# Remote.net
KiCad netlist of a schematic drawn in EAGLE
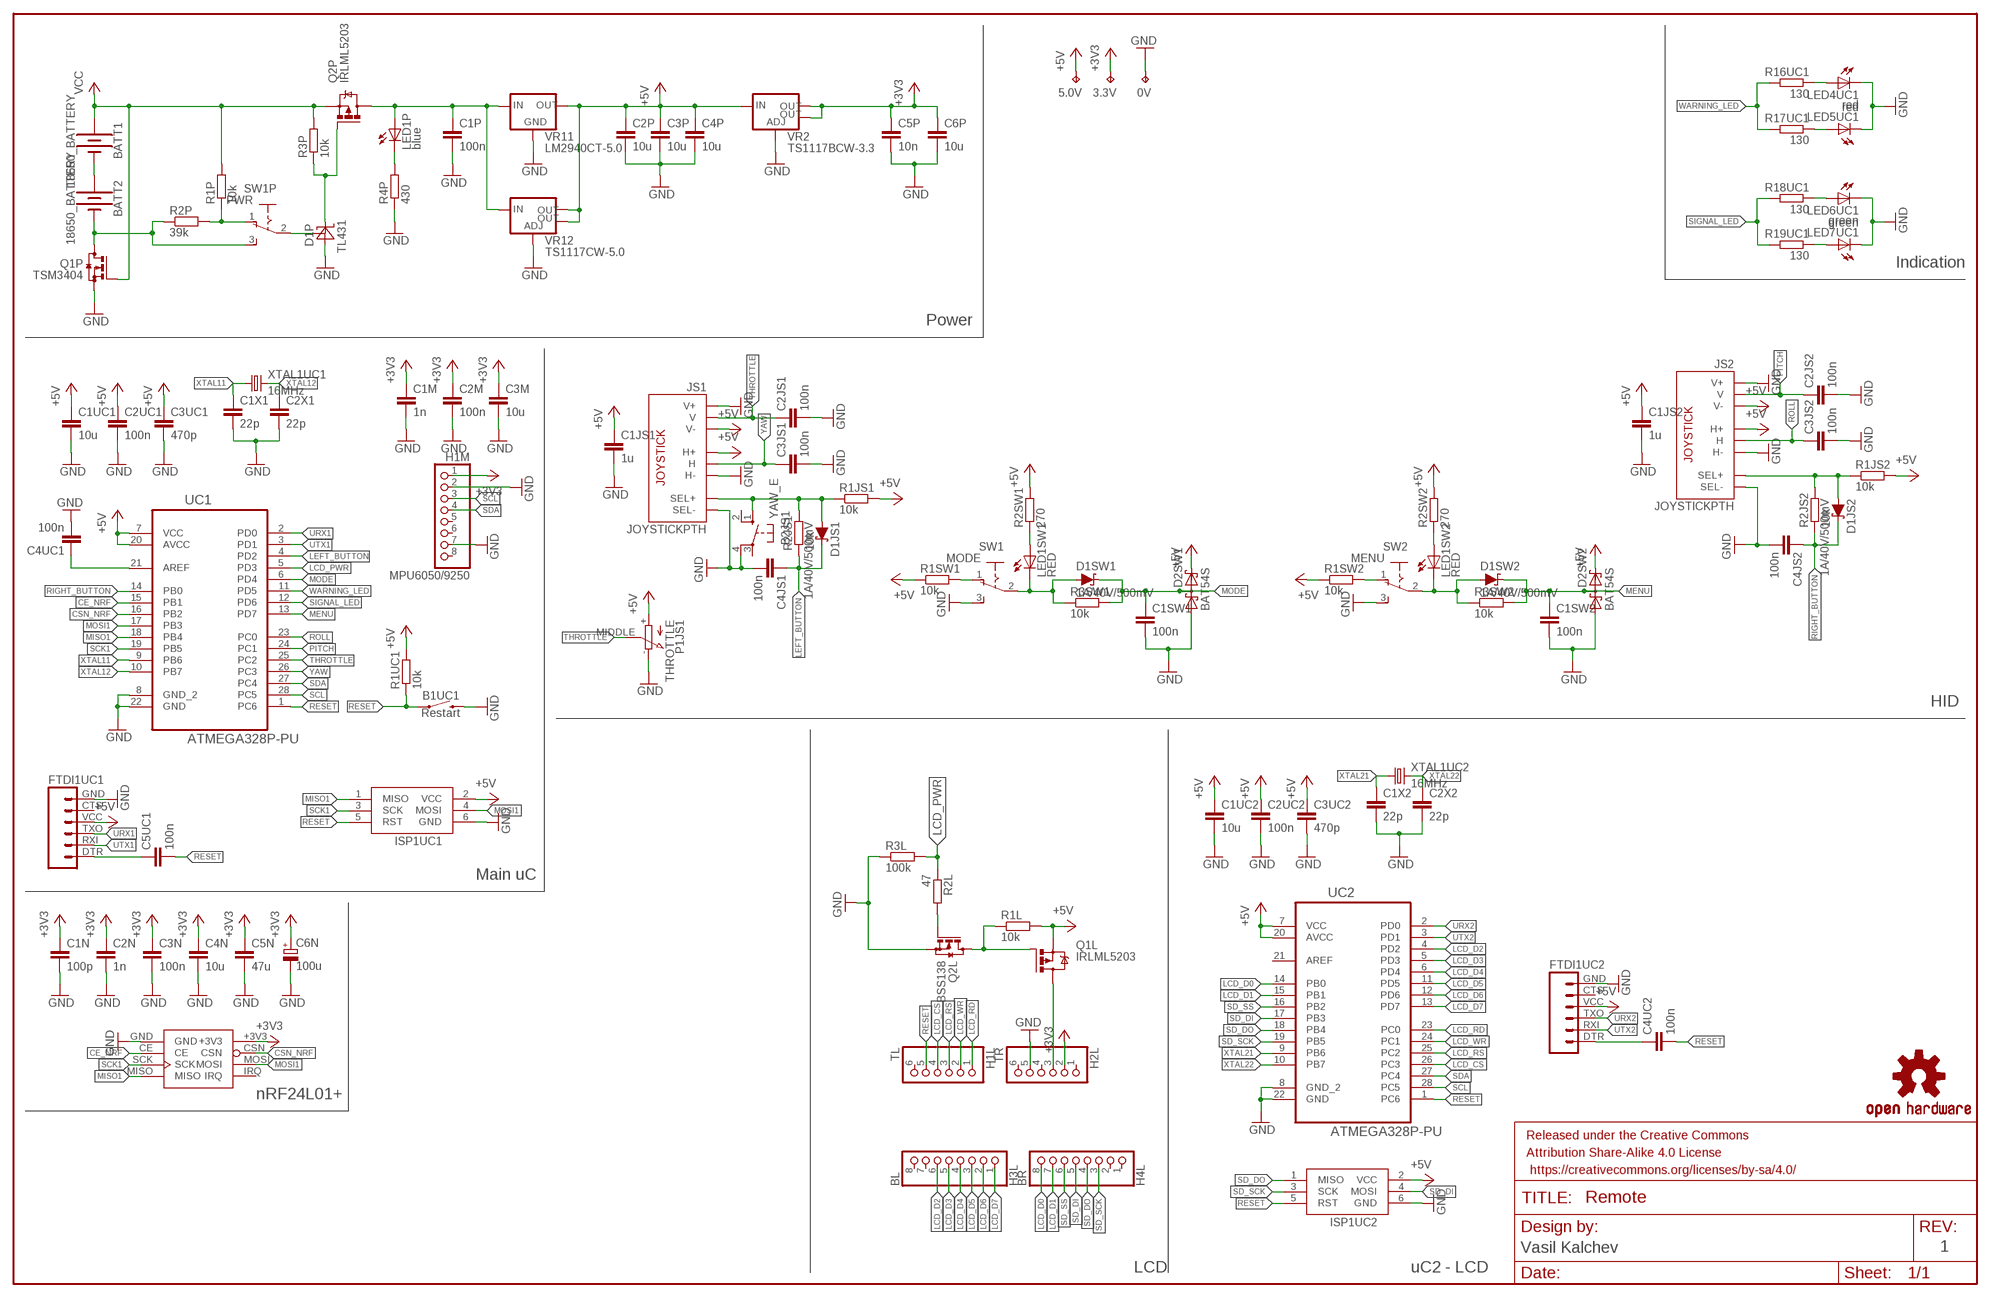
[diagram p0: schematic, sheet 1]

(export (version "E")
  (design (tool "Eeschema 10.0.6"))
  (components
    (comp (ref "0V")
      (value "TPTP10SQ")
      (footprint "eagle-import:TP10SQ")
      (libsource (lib "eagle-import") (part "TPTP10SQ"))
    )
    (comp (ref "3.3V")
      (value "TPTP10SQ")
      (footprint "eagle-import:TP10SQ")
      (libsource (lib "eagle-import") (part "TPTP10SQ"))
    )
    (comp (ref "5.0V")
      (value "TPTP10SQ")
      (footprint "eagle-import:TP10SQ")
      (libsource (lib "eagle-import") (part "TPTP10SQ"))
    )
    (comp (ref "B1")
      (value "nRF24L01+")
      (footprint "eagle-import:NRF24L01+_PA_LNA")
      (libsource (lib "eagle-import") (part "NRF24L01+_PA_LNA_BREAKOUT"))
    )
    (comp (ref "B1UC1")
      (value "Restart")
      (footprint "eagle-import:TACTILE_SWITCH_SMD_6.0X3.5MM")
      (libsource (lib "eagle-import") (part "MOMENTARY-SWITCH-SPST-SMD-6.0X3.5MM"))
    )
    (comp (ref "B2JS1")
      (value "YAW_E")
      (footprint "eagle-import:B3F-40XX")
      (fields (field (name "MF") "OMRON COMPONENTS USA") (field (name "MPN") "B3F-4000"))
      (libsource (lib "eagle-import") (part "40-XX"))
    )
    (comp (ref "BATT1")
      (value "18650_BATTERY")
      (footprint "eagle-import:BATTERY_HOLDER_18650")
      (libsource (lib "eagle-import") (part "18650_BATTERY"))
    )
    (comp (ref "BATT2")
      (value "18650_BATTERY")
      (footprint "eagle-import:BATTERY_HOLDER_18650")
      (libsource (lib "eagle-import") (part "18650_BATTERY"))
    )
    (comp (ref "C1JS1")
      (value "1u")
      (footprint "eagle-import:C1206")
      (libsource (lib "eagle-import") (part "C-EUC1206"))
    )
    (comp (ref "C1JS2")
      (value "1u")
      (footprint "eagle-import:C1206")
      (libsource (lib "eagle-import") (part "C-EUC1206"))
    )
    (comp (ref "C1M")
      (value "1n")
      (footprint "eagle-import:C1206")
      (libsource (lib "eagle-import") (part "C-EUC1206"))
    )
    (comp (ref "C1N")
      (value "100p")
      (footprint "eagle-import:C1206")
      (libsource (lib "eagle-import") (part "C-EUC1206"))
    )
    (comp (ref "C1P")
      (value "100n")
      (footprint "eagle-import:C1206")
      (libsource (lib "eagle-import") (part "C-EUC1206"))
    )
    (comp (ref "C1SW1")
      (value "100n")
      (footprint "eagle-import:C1206")
      (libsource (lib "eagle-import") (part "resistor_348_C-EUC1206"))
    )
    (comp (ref "C1SW2")
      (value "100n")
      (footprint "eagle-import:C1206")
      (libsource (lib "eagle-import") (part "resistor_348_C-EUC1206"))
    )
    (comp (ref "C1UC1")
      (value "10u")
      (footprint "eagle-import:C1206")
      (libsource (lib "eagle-import") (part "C-EUC1206"))
    )
    (comp (ref "C1UC2")
      (value "10u")
      (footprint "eagle-import:C1206")
      (libsource (lib "eagle-import") (part "C-EUC1206"))
    )
    (comp (ref "C1X1")
      (value "22p")
      (footprint "eagle-import:C1206")
      (libsource (lib "eagle-import") (part "C-EUC1206"))
    )
    (comp (ref "C1X2")
      (value "22p")
      (footprint "eagle-import:C1206")
      (libsource (lib "eagle-import") (part "C-EUC1206"))
    )
    (comp (ref "C2JS1")
      (value "100n")
      (footprint "eagle-import:C1206")
      (libsource (lib "eagle-import") (part "resistor_348_C-EUC1206"))
    )
    (comp (ref "C2JS2")
      (value "100n")
      (footprint "eagle-import:C1206")
      (libsource (lib "eagle-import") (part "resistor_348_C-EUC1206"))
    )
    (comp (ref "C2M")
      (value "100n")
      (footprint "eagle-import:C1206")
      (libsource (lib "eagle-import") (part "C-EUC1206"))
    )
    (comp (ref "C2N")
      (value "1n")
      (footprint "eagle-import:C1206")
      (libsource (lib "eagle-import") (part "C-EUC1206"))
    )
    (comp (ref "C2P")
      (value "10u")
      (footprint "eagle-import:C1206")
      (libsource (lib "eagle-import") (part "C-EUC1206"))
    )
    (comp (ref "C2UC1")
      (value "100n")
      (footprint "eagle-import:C1206")
      (libsource (lib "eagle-import") (part "C-EUC1206"))
    )
    (comp (ref "C2UC2")
      (value "100n")
      (footprint "eagle-import:C1206")
      (libsource (lib "eagle-import") (part "C-EUC1206"))
    )
    (comp (ref "C2X1")
      (value "22p")
      (footprint "eagle-import:C1206")
      (libsource (lib "eagle-import") (part "C-EUC1206"))
    )
    (comp (ref "C2X2")
      (value "22p")
      (footprint "eagle-import:C1206")
      (libsource (lib "eagle-import") (part "C-EUC1206"))
    )
    (comp (ref "C3JS1")
      (value "100n")
      (footprint "eagle-import:C1206")
      (libsource (lib "eagle-import") (part "resistor_348_C-EUC1206"))
    )
    (comp (ref "C3JS2")
      (value "100n")
      (footprint "eagle-import:C1206")
      (libsource (lib "eagle-import") (part "resistor_348_C-EUC1206"))
    )
    (comp (ref "C3M")
      (value "10u")
      (footprint "eagle-import:C1206")
      (libsource (lib "eagle-import") (part "C-EUC1206"))
    )
    (comp (ref "C3N")
      (value "100n")
      (footprint "eagle-import:C1206")
      (libsource (lib "eagle-import") (part "C-EUC1206"))
    )
    (comp (ref "C3P")
      (value "10u")
      (footprint "eagle-import:C1206")
      (libsource (lib "eagle-import") (part "C-EUC1206"))
    )
    (comp (ref "C3UC1")
      (value "470p")
      (footprint "eagle-import:C1206")
      (libsource (lib "eagle-import") (part "C-EUC1206"))
    )
    (comp (ref "C3UC2")
      (value "470p")
      (footprint "eagle-import:C1206")
      (libsource (lib "eagle-import") (part "C-EUC1206"))
    )
    (comp (ref "C4JS1")
      (value "100n")
      (footprint "eagle-import:C1206")
      (libsource (lib "eagle-import") (part "resistor_348_C-EUC1206"))
    )
    (comp (ref "C4JS2")
      (value "100n")
      (footprint "eagle-import:C1206")
      (libsource (lib "eagle-import") (part "resistor_348_C-EUC1206"))
    )
    (comp (ref "C4N")
      (value "10u")
      (footprint "eagle-import:C1206")
      (libsource (lib "eagle-import") (part "C-EUC1206"))
    )
    (comp (ref "C4P")
      (value "10u")
      (footprint "eagle-import:C1206")
      (libsource (lib "eagle-import") (part "C-EUC1206"))
    )
    (comp (ref "C4UC1")
      (value "100n")
      (footprint "eagle-import:C1206")
      (libsource (lib "eagle-import") (part "C-EUC1206"))
    )
    (comp (ref "C4UC2")
      (value "100n")
      (footprint "eagle-import:C1206")
      (libsource (lib "eagle-import") (part "C-EUC1206"))
    )
    (comp (ref "C5N")
      (value "47u")
      (footprint "eagle-import:C3225")
      (libsource (lib "eagle-import") (part "C-EUC3225"))
    )
    (comp (ref "C5P")
      (value "10n")
      (footprint "eagle-import:C1206")
      (libsource (lib "eagle-import") (part "C-EUC1206"))
    )
    (comp (ref "C5UC1")
      (value "100n")
      (footprint "eagle-import:C1206")
      (libsource (lib "eagle-import") (part "C-EUC1206"))
    )
    (comp (ref "C6N")
      (value "100u")
      (footprint "eagle-import:153CLV-0505")
      (libsource (lib "eagle-import") (part "CPOL-EU153CLV-0505"))
    )
    (comp (ref "C6P")
      (value "10u")
      (footprint "eagle-import:C1206")
      (libsource (lib "eagle-import") (part "C-EUC1206"))
    )
    (comp (ref "D1JS1")
      (value "1A/40V/500mV")
      (footprint "eagle-import:SMA-DIODE")
      (libsource (lib "eagle-import") (part "DIODE-SCHOTTKY-SS14"))
    )
    (comp (ref "D1JS2")
      (value "1A/40V/500mV")
      (footprint "eagle-import:SMA-DIODE")
      (libsource (lib "eagle-import") (part "DIODE-SCHOTTKY-SS14"))
    )
    (comp (ref "D1P")
      (value "TL431")
      (footprint "eagle-import:SO-8")
      (libsource (lib "eagle-import") (part "TL431-SO8"))
    )
    (comp (ref "D1SW1")
      (value "1A/40V/500mV")
      (footprint "eagle-import:SMA-DIODE")
      (libsource (lib "eagle-import") (part "DIODE-SCHOTTKY-SS14"))
    )
    (comp (ref "D1SW2")
      (value "1A/40V/500mV")
      (footprint "eagle-import:SMA-DIODE")
      (libsource (lib "eagle-import") (part "DIODE-SCHOTTKY-SS14"))
    )
    (comp (ref "D2SW1")
      (value "BAT54S")
      (footprint "eagle-import:SOT23")
      (libsource (lib "eagle-import") (part "BAT54S"))
    )
    (comp (ref "D2SW2")
      (value "BAT54S")
      (footprint "eagle-import:SOT23")
      (libsource (lib "eagle-import") (part "BAT54S"))
    )
    (comp (ref "FRAME2")
      (value "FRAME-LEDGER")
      (footprint "eagle-import:CREATIVE_COMMONS")
      (libsource (lib "eagle-import") (part "FRAME-LEDGER"))
    )
    (comp (ref "FTDI1UC1")
      (value "FTDI_BASICPTH")
      (footprint "eagle-import:FTDI_BASIC")
      (libsource (lib "eagle-import") (part "FTDI_BASICPTH"))
    )
    (comp (ref "FTDI1UC2")
      (value "FTDI_BASICPTH")
      (footprint "eagle-import:FTDI_BASIC")
      (libsource (lib "eagle-import") (part "FTDI_BASICPTH"))
    )
    (comp (ref "H1L")
      (value "TL")
      (footprint "eagle-import:1X06")
      (libsource (lib "eagle-import") (part "PINHD-1X6_2.54"))
    )
    (comp (ref "H1M")
      (value "MPU6050/9250")
      (footprint "eagle-import:1X08")
      (libsource (lib "eagle-import") (part "PINHD-1X8_2.54"))
    )
    (comp (ref "H2L")
      (value "TR")
      (footprint "eagle-import:1X06")
      (libsource (lib "eagle-import") (part "PINHD-1X6_2.54"))
    )
    (comp (ref "H3L")
      (value "BL")
      (footprint "eagle-import:1X08")
      (libsource (lib "eagle-import") (part "PINHD-1X8_2.54"))
    )
    (comp (ref "H4L")
      (value "BR")
      (footprint "eagle-import:1X08")
      (libsource (lib "eagle-import") (part "PINHD-1X8_2.54"))
    )
    (comp (ref "ISP1UC1")
      (value "AVRISP-6")
      (footprint "eagle-import:AVRISP")
      (libsource (lib "eagle-import") (part "AVRISP-6"))
    )
    (comp (ref "ISP1UC2")
      (value "AVRISP-6")
      (footprint "eagle-import:AVRISP")
      (libsource (lib "eagle-import") (part "AVRISP-6"))
    )
    (comp (ref "JS1")
      (value "JOYSTICKPTH")
      (footprint "eagle-import:JOYSTICK")
      (libsource (lib "eagle-import") (part "JOYSTICKPTH"))
    )
    (comp (ref "JS2")
      (value "JOYSTICKPTH")
      (footprint "eagle-import:JOYSTICK")
      (libsource (lib "eagle-import") (part "JOYSTICKPTH"))
    )
    (comp (ref "LED1P")
      (value "blue")
      (footprint "eagle-import:SML1206")
      (libsource (lib "eagle-import") (part "LEDSML1206"))
    )
    (comp (ref "LED1SW1")
      (value "RED")
      (footprint "eagle-import:SML1206")
      (libsource (lib "eagle-import") (part "LEDSML1206"))
    )
    (comp (ref "LED1SW2")
      (value "RED")
      (footprint "eagle-import:SML1206")
      (libsource (lib "eagle-import") (part "LEDSML1206"))
    )
    (comp (ref "LED4UC1")
      (value "red")
      (footprint "eagle-import:SML1206")
      (libsource (lib "eagle-import") (part "LEDSML1206"))
    )
    (comp (ref "LED5UC1")
      (value "red")
      (footprint "eagle-import:1206")
      (libsource (lib "eagle-import") (part "LEDSMT1206"))
    )
    (comp (ref "LED6UC1")
      (value "green")
      (footprint "eagle-import:SML1206")
      (libsource (lib "eagle-import") (part "LEDSML1206"))
    )
    (comp (ref "LED7UC1")
      (value "green")
      (footprint "eagle-import:1206")
      (libsource (lib "eagle-import") (part "LEDSMT1206"))
    )
    (comp (ref "LOGO1")
      (value "OSHW-LOGOL-COPPER")
      (footprint "eagle-import:OSHW-LOGO-L_COPPER")
      (libsource (lib "eagle-import") (part "OSHW-LOGOL-COPPER"))
    )
    (comp (ref "P1JS1")
      (value "THROTTLE")
      (footprint "eagle-import:SLIDE_POTENTIOMETER")
      (libsource (lib "eagle-import") (part "SLIDE_POTENTIOMETER_EU"))
    )
    (comp (ref "Q1L")
      (value "IRLML5203")
      (footprint "eagle-import:MICRO3")
      (libsource (lib "eagle-import") (part "IRLML5203"))
    )
    (comp (ref "Q1P")
      (value "TSM3404")
      (footprint "eagle-import:SOT23")
      (libsource (lib "eagle-import") (part "BSS123"))
    )
    (comp (ref "Q2L")
      (value "BSS138")
      (footprint "eagle-import:SOT23")
      (libsource (lib "eagle-import") (part "transistor-small-signal_401_BSS123"))
    )
    (comp (ref "Q2P")
      (value "IRLML5203")
      (footprint "eagle-import:MICRO3")
      (libsource (lib "eagle-import") (part "IRLML5203"))
    )
    (comp (ref "R1JS1")
      (value "10k")
      (footprint "eagle-import:R1206")
      (libsource (lib "eagle-import") (part "R-EU_R1206"))
    )
    (comp (ref "R1JS2")
      (value "10k")
      (footprint "eagle-import:R1206")
      (libsource (lib "eagle-import") (part "R-EU_R1206"))
    )
    (comp (ref "R1L")
      (value "10k")
      (footprint "eagle-import:R1206")
      (libsource (lib "eagle-import") (part "rcl_334_R-EU_R1206"))
    )
    (comp (ref "R1P")
      (value "10k")
      (footprint "eagle-import:R1206")
      (libsource (lib "eagle-import") (part "rcl_334_R-EU_R1206"))
    )
    (comp (ref "R1SW1")
      (value "10k")
      (footprint "eagle-import:R1206")
      (libsource (lib "eagle-import") (part "R-EU_R1206"))
    )
    (comp (ref "R1SW2")
      (value "10k")
      (footprint "eagle-import:R1206")
      (libsource (lib "eagle-import") (part "R-EU_R1206"))
    )
    (comp (ref "R1UC1")
      (value "10k")
      (footprint "eagle-import:R1206")
      (libsource (lib "eagle-import") (part "rcl_334_R-EU_R1206"))
    )
    (comp (ref "R2JS1")
      (value "10k")
      (footprint "eagle-import:R1206")
      (libsource (lib "eagle-import") (part "R-EU_R1206"))
    )
    (comp (ref "R2JS2")
      (value "10k")
      (footprint "eagle-import:R1206")
      (libsource (lib "eagle-import") (part "R-EU_R1206"))
    )
    (comp (ref "R2L")
      (value "47")
      (footprint "eagle-import:R1206")
      (libsource (lib "eagle-import") (part "rcl_334_R-EU_R1206"))
    )
    (comp (ref "R2P")
      (value "39k")
      (footprint "eagle-import:R1206")
      (libsource (lib "eagle-import") (part "rcl_334_R-EU_R1206"))
    )
    (comp (ref "R2SW1")
      (value "270")
      (footprint "eagle-import:R1206")
      (libsource (lib "eagle-import") (part "R-EU_R1206"))
    )
    (comp (ref "R2SW2")
      (value "270")
      (footprint "eagle-import:R1206")
      (libsource (lib "eagle-import") (part "R-EU_R1206"))
    )
    (comp (ref "R3L")
      (value "100k")
      (footprint "eagle-import:R1206")
      (libsource (lib "eagle-import") (part "rcl_334_R-EU_R1206"))
    )
    (comp (ref "R3P")
      (value "10k")
      (footprint "eagle-import:R1206")
      (libsource (lib "eagle-import") (part "rcl_334_R-EU_R1206"))
    )
    (comp (ref "R3SW1")
      (value "10k")
      (footprint "eagle-import:R1206")
      (libsource (lib "eagle-import") (part "R-EU_R1206"))
    )
    (comp (ref "R3SW2")
      (value "10k")
      (footprint "eagle-import:R1206")
      (libsource (lib "eagle-import") (part "R-EU_R1206"))
    )
    (comp (ref "R4P")
      (value "430")
      (footprint "eagle-import:R1206")
      (libsource (lib "eagle-import") (part "rcl_334_R-EU_R1206"))
    )
    (comp (ref "R16UC1")
      (value "130")
      (footprint "eagle-import:R1206")
      (libsource (lib "eagle-import") (part "rcl_334_R-EU_R1206"))
    )
    (comp (ref "R17UC1")
      (value "130")
      (footprint "eagle-import:R1206")
      (libsource (lib "eagle-import") (part "rcl_334_R-EU_R1206"))
    )
    (comp (ref "R18UC1")
      (value "130")
      (footprint "eagle-import:R1206")
      (libsource (lib "eagle-import") (part "rcl_334_R-EU_R1206"))
    )
    (comp (ref "R19UC1")
      (value "130")
      (footprint "eagle-import:R1206")
      (libsource (lib "eagle-import") (part "rcl_334_R-EU_R1206"))
    )
    (comp (ref "SW1")
      (value "MODE")
      (footprint "eagle-import:SWITCH_2MM")
      (libsource (lib "eagle-import") (part "SPDT_SWITCH_2MM"))
    )
    (comp (ref "SW1P")
      (value "PWR")
      (footprint "eagle-import:SWITCH_2MM")
      (libsource (lib "eagle-import") (part "SPDT_SWITCH_2MM"))
    )
    (comp (ref "SW2")
      (value "MENU")
      (footprint "eagle-import:SWITCH_2MM")
      (libsource (lib "eagle-import") (part "SPDT_SWITCH_2MM"))
    )
    (comp (ref "UC1")
      (value "ATMEGA328P-PU")
      (footprint "eagle-import:DIP254P762X457-28")
      (libsource (lib "eagle-import") (part "ATMEGA328P-PU"))
    )
    (comp (ref "UC2")
      (value "ATMEGA328P-PU")
      (footprint "eagle-import:DIP254P762X457-28")
      (libsource (lib "eagle-import") (part "ATMEGA328P-PU"))
    )
    (comp (ref "VR2")
      (value "TS1117BCW-3.3")
      (footprint "eagle-import:SOT223")
      (libsource (lib "eagle-import") (part "V_REG_LM1117SOT223"))
    )
    (comp (ref "VR11")
      (value "LM2940CT-5.0")
      (footprint "eagle-import:78XXL")
      (libsource (lib "eagle-import") (part "78XXL"))
    )
    (comp (ref "VR12")
      (value "TS1117CW-5.0")
      (footprint "eagle-import:SOT223")
      (libsource (lib "eagle-import") (part "V_REG_LM1117SOT223"))
    )
    (comp (ref "XTAL1UC1")
      (value "16MHz")
      (footprint "eagle-import:HC49_S")
      (libsource (lib "eagle-import") (part "CRYSTALHC49S"))
    )
    (comp (ref "XTAL1UC2")
      (value "16MHz")
      (footprint "eagle-import:HC49_S")
      (libsource (lib "eagle-import") (part "CRYSTALHC49S"))
    )
  )
  (nets
    (net (code "1") (name "+3V3") (class "Default")
      (node (ref "3.3V") (pin "TP") (pinfunction "TP_TP") (pintype "input"))
      (node (ref "B1") (pin "+3V3") (pinfunction "+3V3_+3V3") (pintype "power_in"))
      (node (ref "C1M") (pin "1") (pinfunction "1_1") (pintype "passive"))
      (node (ref "C1N") (pin "1") (pinfunction "1_1") (pintype "passive"))
      (node (ref "C2M") (pin "1") (pinfunction "1_1") (pintype "passive"))
      (node (ref "C2N") (pin "1") (pinfunction "1_1") (pintype "passive"))
      (node (ref "C3M") (pin "1") (pinfunction "1_1") (pintype "passive"))
      (node (ref "C3N") (pin "1") (pinfunction "1_1") (pintype "passive"))
      (node (ref "C4N") (pin "1") (pinfunction "1_1") (pintype "passive"))
      (node (ref "C5N") (pin "1") (pinfunction "1_1") (pintype "passive"))
      (node (ref "C5P") (pin "1") (pinfunction "1_1") (pintype "passive"))
      (node (ref "C6N") (pin "+") (pinfunction "+_+") (pintype "passive"))
      (node (ref "C6P") (pin "1") (pinfunction "1_1") (pintype "passive"))
      (node (ref "H1M") (pin "1") (pinfunction "1_1") (pintype "passive"))
      (node (ref "H2L") (pin "2") (pinfunction "2_2") (pintype "passive"))
      (node (ref "VR2") (pin "2") (pinfunction "OUT_2") (pintype "output"))
      (node (ref "VR2") (pin "4") (pinfunction "OUT_4") (pintype "output"))
    )
    (net (code "2") (name "+5V") (class "Default")
      (node (ref "5.0V") (pin "TP") (pinfunction "TP_TP") (pintype "input"))
      (node (ref "C1JS1") (pin "1") (pinfunction "1_1") (pintype "passive"))
      (node (ref "C1JS2") (pin "1") (pinfunction "1_1") (pintype "passive"))
      (node (ref "C1UC1") (pin "1") (pinfunction "1_1") (pintype "passive"))
      (node (ref "C1UC2") (pin "1") (pinfunction "1_1") (pintype "passive"))
      (node (ref "C2P") (pin "1") (pinfunction "1_1") (pintype "passive"))
      (node (ref "C2UC1") (pin "1") (pinfunction "1_1") (pintype "passive"))
      (node (ref "C2UC2") (pin "1") (pinfunction "1_1") (pintype "passive"))
      (node (ref "C3P") (pin "1") (pinfunction "1_1") (pintype "passive"))
      (node (ref "C3UC1") (pin "1") (pinfunction "1_1") (pintype "passive"))
      (node (ref "C3UC2") (pin "1") (pinfunction "1_1") (pintype "passive"))
      (node (ref "C4P") (pin "1") (pinfunction "1_1") (pintype "passive"))
      (node (ref "D2SW1") (pin "2") (pinfunction "C2_2") (pintype "passive"))
      (node (ref "D2SW2") (pin "2") (pinfunction "C2_2") (pintype "passive"))
      (node (ref "FTDI1UC1") (pin "VCC") (pinfunction "4_VCC") (pintype "passive"))
      (node (ref "FTDI1UC2") (pin "VCC") (pinfunction "4_VCC") (pintype "passive"))
      (node (ref "ISP1UC1") (pin "2") (pinfunction "VCC_2") (pintype "power_in"))
      (node (ref "ISP1UC2") (pin "2") (pinfunction "VCC_2") (pintype "power_in"))
      (node (ref "JS1") (pin "H1") (pinfunction "H+_H1") (pintype "bidirectional"))
      (node (ref "JS1") (pin "V3") (pinfunction "V-_V3") (pintype "bidirectional"))
      (node (ref "JS2") (pin "H1") (pinfunction "H+_H1") (pintype "bidirectional"))
      (node (ref "JS2") (pin "V3") (pinfunction "V-_V3") (pintype "bidirectional"))
      (node (ref "P1JS1") (pin "+") (pinfunction "+_+") (pintype "passive"))
      (node (ref "Q1L") (pin "2") (pinfunction "S_2") (pintype "passive"))
      (node (ref "R1JS1") (pin "2") (pinfunction "2_2") (pintype "passive"))
      (node (ref "R1JS2") (pin "2") (pinfunction "2_2") (pintype "passive"))
      (node (ref "R1L") (pin "2") (pinfunction "2_2") (pintype "passive"))
      (node (ref "R1SW1") (pin "1") (pinfunction "1_1") (pintype "passive"))
      (node (ref "R1SW2") (pin "1") (pinfunction "1_1") (pintype "passive"))
      (node (ref "R1UC1") (pin "2") (pinfunction "2_2") (pintype "passive"))
      (node (ref "R2SW1") (pin "2") (pinfunction "2_2") (pintype "passive"))
      (node (ref "R2SW2") (pin "2") (pinfunction "2_2") (pintype "passive"))
      (node (ref "UC1") (pin "20") (pinfunction "AVCC_20") (pintype "power_in"))
      (node (ref "UC1") (pin "7") (pinfunction "VCC_7") (pintype "power_in"))
      (node (ref "UC2") (pin "20") (pinfunction "AVCC_20") (pintype "power_in"))
      (node (ref "UC2") (pin "7") (pinfunction "VCC_7") (pintype "power_in"))
      (node (ref "VR11") (pin "OUT") (pinfunction "OUT_OUT") (pintype "passive"))
      (node (ref "VR12") (pin "2") (pinfunction "OUT_2") (pintype "output"))
      (node (ref "VR12") (pin "4") (pinfunction "OUT_4") (pintype "output"))
      (node (ref "VR2") (pin "3") (pinfunction "IN_3") (pintype "input"))
    )
    (net (code "3") (name "CE_NRF") (class "Default")
      (node (ref "B1") (pin "CE") (pinfunction "CE_CE") (pintype "input"))
      (node (ref "UC1") (pin "15") (pinfunction "PB1_15") (pintype "bidirectional"))
    )
    (net (code "4") (name "CSN_NRF") (class "Default")
      (node (ref "B1") (pin "CSN") (pinfunction "CSN_CSN") (pintype "input"))
      (node (ref "UC1") (pin "16") (pinfunction "PB2_16") (pintype "bidirectional"))
    )
    (net (code "5") (name "GND") (class "Default")
      (node (ref "0V") (pin "TP") (pinfunction "TP_TP") (pintype "input"))
      (node (ref "B1") (pin "GND") (pinfunction "GND_GND") (pintype "power_in"))
      (node (ref "B1UC1") (pin "2") (pinfunction "2_2") (pintype "passive"))
      (node (ref "B2JS1") (pin "4") (pinfunction "P1_4") (pintype "passive"))
      (node (ref "C1JS1") (pin "2") (pinfunction "2_2") (pintype "passive"))
      (node (ref "C1JS2") (pin "2") (pinfunction "2_2") (pintype "passive"))
      (node (ref "C1M") (pin "2") (pinfunction "2_2") (pintype "passive"))
      (node (ref "C1N") (pin "2") (pinfunction "2_2") (pintype "passive"))
      (node (ref "C1P") (pin "2") (pinfunction "2_2") (pintype "passive"))
      (node (ref "C1SW1") (pin "2") (pinfunction "2_2") (pintype "passive"))
      (node (ref "C1SW2") (pin "2") (pinfunction "2_2") (pintype "passive"))
      (node (ref "C1UC1") (pin "2") (pinfunction "2_2") (pintype "passive"))
      (node (ref "C1UC2") (pin "2") (pinfunction "2_2") (pintype "passive"))
      (node (ref "C1X1") (pin "2") (pinfunction "2_2") (pintype "passive"))
      (node (ref "C1X2") (pin "2") (pinfunction "2_2") (pintype "passive"))
      (node (ref "C2JS1") (pin "2") (pinfunction "2_2") (pintype "passive"))
      (node (ref "C2JS2") (pin "2") (pinfunction "2_2") (pintype "passive"))
      (node (ref "C2M") (pin "2") (pinfunction "2_2") (pintype "passive"))
      (node (ref "C2N") (pin "2") (pinfunction "2_2") (pintype "passive"))
      (node (ref "C2P") (pin "2") (pinfunction "2_2") (pintype "passive"))
      (node (ref "C2UC1") (pin "2") (pinfunction "2_2") (pintype "passive"))
      (node (ref "C2UC2") (pin "2") (pinfunction "2_2") (pintype "passive"))
      (node (ref "C2X1") (pin "2") (pinfunction "2_2") (pintype "passive"))
      (node (ref "C2X2") (pin "2") (pinfunction "2_2") (pintype "passive"))
      (node (ref "C3JS1") (pin "2") (pinfunction "2_2") (pintype "passive"))
      (node (ref "C3JS2") (pin "2") (pinfunction "2_2") (pintype "passive"))
      (node (ref "C3M") (pin "2") (pinfunction "2_2") (pintype "passive"))
      (node (ref "C3N") (pin "2") (pinfunction "2_2") (pintype "passive"))
      (node (ref "C3P") (pin "2") (pinfunction "2_2") (pintype "passive"))
      (node (ref "C3UC1") (pin "2") (pinfunction "2_2") (pintype "passive"))
      (node (ref "C3UC2") (pin "2") (pinfunction "2_2") (pintype "passive"))
      (node (ref "C4JS1") (pin "2") (pinfunction "2_2") (pintype "passive"))
      (node (ref "C4JS2") (pin "2") (pinfunction "2_2") (pintype "passive"))
      (node (ref "C4N") (pin "2") (pinfunction "2_2") (pintype "passive"))
      (node (ref "C4P") (pin "2") (pinfunction "2_2") (pintype "passive"))
      (node (ref "C4UC1") (pin "2") (pinfunction "2_2") (pintype "passive"))
      (node (ref "C5N") (pin "2") (pinfunction "2_2") (pintype "passive"))
      (node (ref "C5P") (pin "2") (pinfunction "2_2") (pintype "passive"))
      (node (ref "C6N") (pin "-") (pinfunction "-_-") (pintype "passive"))
      (node (ref "C6P") (pin "2") (pinfunction "2_2") (pintype "passive"))
      (node (ref "D1P") (pin "2") (pinfunction "ANODE_2") (pintype "passive"))
      (node (ref "D1P") (pin "3") (pinfunction "ANODE_3") (pintype "passive"))
      (node (ref "D1P") (pin "6") (pinfunction "ANODE_6") (pintype "passive"))
      (node (ref "D1P") (pin "7") (pinfunction "ANODE_7") (pintype "passive"))
      (node (ref "D2SW1") (pin "1") (pinfunction "A1_1") (pintype "passive"))
      (node (ref "D2SW2") (pin "1") (pinfunction "A1_1") (pintype "passive"))
      (node (ref "FTDI1UC1") (pin "GND") (pinfunction "6_GND") (pintype "passive"))
      (node (ref "FTDI1UC2") (pin "GND") (pinfunction "6_GND") (pintype "passive"))
      (node (ref "H1M") (pin "2") (pinfunction "2_2") (pintype "passive"))
      (node (ref "H1M") (pin "7") (pinfunction "7_7") (pintype "passive"))
      (node (ref "H2L") (pin "5") (pinfunction "5_5") (pintype "passive"))
      (node (ref "ISP1UC1") (pin "6") (pinfunction "GND_6") (pintype "power_in"))
      (node (ref "ISP1UC2") (pin "6") (pinfunction "GND_6") (pintype "power_in"))
      (node (ref "JS1") (pin "B2A") (pinfunction "SEL-_B2A") (pintype "bidirectional"))
      (node (ref "JS1") (pin "H3") (pinfunction "H-_H3") (pintype "bidirectional"))
      (node (ref "JS1") (pin "V1") (pinfunction "V+_V1") (pintype "bidirectional"))
      (node (ref "JS2") (pin "B2A") (pinfunction "SEL-_B2A") (pintype "bidirectional"))
      (node (ref "JS2") (pin "H3") (pinfunction "H-_H3") (pintype "bidirectional"))
      (node (ref "JS2") (pin "V1") (pinfunction "V+_V1") (pintype "bidirectional"))
      (node (ref "LED4UC1") (pin "C") (pinfunction "C_C") (pintype "passive"))
      (node (ref "LED5UC1") (pin "C") (pinfunction "C_C") (pintype "passive"))
      (node (ref "LED6UC1") (pin "C") (pinfunction "C_C") (pintype "passive"))
      (node (ref "LED7UC1") (pin "C") (pinfunction "C_C") (pintype "passive"))
      (node (ref "P1JS1") (pin "-") (pinfunction "-_-") (pintype "passive"))
      (node (ref "Q1P") (pin "2") (pinfunction "S_2") (pintype "passive"))
      (node (ref "Q2L") (pin "2") (pinfunction "S_2") (pintype "passive"))
      (node (ref "R3L") (pin "1") (pinfunction "1_1") (pintype "passive"))
      (node (ref "R4P") (pin "1") (pinfunction "1_1") (pintype "passive"))
      (node (ref "SW1") (pin "3") (pinfunction "3_3") (pintype "passive"))
      (node (ref "SW2") (pin "3") (pinfunction "3_3") (pintype "passive"))
      (node (ref "UC1") (pin "22") (pinfunction "GND_22") (pintype "passive"))
      (node (ref "UC1") (pin "8") (pinfunction "GND_2_8") (pintype "passive"))
      (node (ref "UC2") (pin "22") (pinfunction "GND_22") (pintype "passive"))
      (node (ref "UC2") (pin "8") (pinfunction "GND_2_8") (pintype "passive"))
      (node (ref "VR11") (pin "GND") (pinfunction "GND_GND") (pintype "input"))
      (node (ref "VR12") (pin "1") (pinfunction "ADJ_1") (pintype "input"))
      (node (ref "VR2") (pin "1") (pinfunction "ADJ_1") (pintype "input"))
    )
    (net (code "6") (name "LCD_CS") (class "Default")
      (node (ref "H1L") (pin "4") (pinfunction "4_4") (pintype "passive"))
      (node (ref "UC2") (pin "26") (pinfunction "PC3_26") (pintype "bidirectional"))
    )
    (net (code "7") (name "LCD_D0") (class "Default")
      (node (ref "H4L") (pin "8") (pinfunction "8_8") (pintype "passive"))
      (node (ref "UC2") (pin "14") (pinfunction "PB0_14") (pintype "bidirectional"))
    )
    (net (code "8") (name "LCD_D1") (class "Default")
      (node (ref "H4L") (pin "7") (pinfunction "7_7") (pintype "passive"))
      (node (ref "UC2") (pin "15") (pinfunction "PB1_15") (pintype "bidirectional"))
    )
    (net (code "9") (name "LCD_D2") (class "Default")
      (node (ref "H3L") (pin "6") (pinfunction "6_6") (pintype "passive"))
      (node (ref "UC2") (pin "4") (pinfunction "PD2_4") (pintype "bidirectional"))
    )
    (net (code "10") (name "LCD_D3") (class "Default")
      (node (ref "H3L") (pin "5") (pinfunction "5_5") (pintype "passive"))
      (node (ref "UC2") (pin "5") (pinfunction "PD3_5") (pintype "bidirectional"))
    )
    (net (code "11") (name "LCD_D4") (class "Default")
      (node (ref "H3L") (pin "4") (pinfunction "4_4") (pintype "passive"))
      (node (ref "UC2") (pin "6") (pinfunction "PD4_6") (pintype "bidirectional"))
    )
    (net (code "12") (name "LCD_D5") (class "Default")
      (node (ref "H3L") (pin "3") (pinfunction "3_3") (pintype "passive"))
      (node (ref "UC2") (pin "11") (pinfunction "PD5_11") (pintype "bidirectional"))
    )
    (net (code "13") (name "LCD_D6") (class "Default")
      (node (ref "H3L") (pin "2") (pinfunction "2_2") (pintype "passive"))
      (node (ref "UC2") (pin "12") (pinfunction "PD6_12") (pintype "bidirectional"))
    )
    (net (code "14") (name "LCD_D7") (class "Default")
      (node (ref "H3L") (pin "1") (pinfunction "1_1") (pintype "passive"))
      (node (ref "UC2") (pin "13") (pinfunction "PD7_13") (pintype "bidirectional"))
    )
    (net (code "15") (name "LCD_PWR") (class "Default")
      (node (ref "R2L") (pin "1") (pinfunction "1_1") (pintype "passive"))
      (node (ref "R3L") (pin "2") (pinfunction "2_2") (pintype "passive"))
      (node (ref "UC1") (pin "5") (pinfunction "PD3_5") (pintype "bidirectional"))
    )
    (net (code "16") (name "LCD_RD") (class "Default")
      (node (ref "H1L") (pin "1") (pinfunction "1_1") (pintype "passive"))
      (node (ref "UC2") (pin "23") (pinfunction "PC0_23") (pintype "bidirectional"))
    )
    (net (code "17") (name "LCD_RS") (class "Default")
      (node (ref "H1L") (pin "3") (pinfunction "3_3") (pintype "passive"))
      (node (ref "UC2") (pin "25") (pinfunction "PC2_25") (pintype "bidirectional"))
    )
    (net (code "18") (name "LCD_WR") (class "Default")
      (node (ref "H1L") (pin "2") (pinfunction "2_2") (pintype "passive"))
      (node (ref "UC2") (pin "24") (pinfunction "PC1_24") (pintype "bidirectional"))
    )
    (net (code "19") (name "LEFT_BUTTON") (class "Default")
      (node (ref "C4JS1") (pin "1") (pinfunction "1_1") (pintype "passive"))
      (node (ref "D1JS1") (pin "C") (pinfunction "C_C") (pintype "passive"))
      (node (ref "R2JS1") (pin "1") (pinfunction "1_1") (pintype "passive"))
      (node (ref "UC1") (pin "4") (pinfunction "PD2_4") (pintype "bidirectional"))
    )
    (net (code "20") (name "MENU") (class "Default")
      (node (ref "C1SW2") (pin "1") (pinfunction "1_1") (pintype "passive"))
      (node (ref "D1SW2") (pin "C") (pinfunction "C_C") (pintype "passive"))
      (node (ref "D2SW2") (pin "3") (pinfunction "C1A2_3") (pintype "passive"))
      (node (ref "R3SW2") (pin "2") (pinfunction "2_2") (pintype "passive"))
      (node (ref "UC1") (pin "13") (pinfunction "PD7_13") (pintype "bidirectional"))
    )
    (net (code "21") (name "MISO1") (class "Default")
      (node (ref "B1") (pin "MISO") (pinfunction "MISO_MISO") (pintype "output"))
      (node (ref "ISP1UC1") (pin "1") (pinfunction "MISO_1") (pintype "input"))
      (node (ref "UC1") (pin "18") (pinfunction "PB4_18") (pintype "bidirectional"))
    )
    (net (code "22") (name "MODE") (class "Default")
      (node (ref "C1SW1") (pin "1") (pinfunction "1_1") (pintype "passive"))
      (node (ref "D1SW1") (pin "C") (pinfunction "C_C") (pintype "passive"))
      (node (ref "D2SW1") (pin "3") (pinfunction "C1A2_3") (pintype "passive"))
      (node (ref "R3SW1") (pin "2") (pinfunction "2_2") (pintype "passive"))
      (node (ref "UC1") (pin "6") (pinfunction "PD4_6") (pintype "bidirectional"))
    )
    (net (code "23") (name "MOSI1") (class "Default")
      (node (ref "B1") (pin "MOSI") (pinfunction "MOSI_MOSI") (pintype "input"))
      (node (ref "ISP1UC1") (pin "4") (pinfunction "MOSI_4") (pintype "output"))
      (node (ref "UC1") (pin "17") (pinfunction "PB3_17") (pintype "bidirectional"))
    )
    (net (code "24") (name "Net-(B2JS1-S)") (class "Default")
      (node (ref "B2JS1") (pin "1") (pinfunction "S_1") (pintype "passive"))
      (node (ref "D1JS1") (pin "A") (pinfunction "A_A") (pintype "passive"))
      (node (ref "JS1") (pin "B1A") (pinfunction "SEL+_B1A") (pintype "bidirectional"))
      (node (ref "R1JS1") (pin "1") (pinfunction "1_1") (pintype "passive"))
      (node (ref "R2JS1") (pin "2") (pinfunction "2_2") (pintype "passive"))
    )
    (net (code "25") (name "Net-(BATT1-Pad-)") (class "Default")
      (node (ref "BATT1") (pin "-") (pinfunction "-_-") (pintype "power_in"))
      (node (ref "BATT2") (pin "+") (pinfunction "+_+") (pintype "power_in"))
    )
    (net (code "26") (name "Net-(D1P-CATHODE)") (class "Default")
      (node (ref "D1P") (pin "1") (pinfunction "CATHODE_1") (pintype "passive"))
      (node (ref "Q2P") (pin "1") (pinfunction "G_1") (pintype "passive"))
      (node (ref "R3P") (pin "1") (pinfunction "1_1") (pintype "passive"))
    )
    (net (code "27") (name "Net-(D1P-REFERENCE)") (class "Default")
      (node (ref "D1P") (pin "8") (pinfunction "REFERENCE_8") (pintype "passive"))
      (node (ref "SW1P") (pin "2") (pinfunction "2_2") (pintype "passive"))
    )
    (net (code "28") (name "Net-(D1SW1-PadA)") (class "Default")
      (node (ref "D1SW1") (pin "A") (pinfunction "A_A") (pintype "passive"))
      (node (ref "LED1SW1") (pin "C") (pinfunction "C_C") (pintype "passive"))
      (node (ref "R3SW1") (pin "1") (pinfunction "1_1") (pintype "passive"))
      (node (ref "SW1") (pin "2") (pinfunction "2_2") (pintype "passive"))
    )
    (net (code "29") (name "Net-(D1SW2-PadA)") (class "Default")
      (node (ref "D1SW2") (pin "A") (pinfunction "A_A") (pintype "passive"))
      (node (ref "LED1SW2") (pin "C") (pinfunction "C_C") (pintype "passive"))
      (node (ref "R3SW2") (pin "1") (pinfunction "1_1") (pintype "passive"))
      (node (ref "SW2") (pin "2") (pinfunction "2_2") (pintype "passive"))
    )
    (net (code "30") (name "Net-(FTDI1UC1-1)") (class "Default")
      (node (ref "C5UC1") (pin "1") (pinfunction "1_1") (pintype "passive"))
      (node (ref "FTDI1UC1") (pin "DTR") (pinfunction "1_DTR") (pintype "passive"))
    )
    (net (code "31") (name "Net-(FTDI1UC2-1)") (class "Default")
      (node (ref "C4UC2") (pin "1") (pinfunction "1_1") (pintype "passive"))
      (node (ref "FTDI1UC2") (pin "DTR") (pinfunction "1_DTR") (pintype "passive"))
    )
    (net (code "32") (name "Net-(JS2-SEL+)") (class "Default")
      (node (ref "D1JS2") (pin "A") (pinfunction "A_A") (pintype "passive"))
      (node (ref "JS2") (pin "B1A") (pinfunction "SEL+_B1A") (pintype "bidirectional"))
      (node (ref "R1JS2") (pin "1") (pinfunction "1_1") (pintype "passive"))
      (node (ref "R2JS2") (pin "2") (pinfunction "2_2") (pintype "passive"))
    )
    (net (code "33") (name "Net-(LED1P-PadC)") (class "Default")
      (node (ref "LED1P") (pin "C") (pinfunction "C_C") (pintype "passive"))
      (node (ref "R4P") (pin "2") (pinfunction "2_2") (pintype "passive"))
    )
    (net (code "34") (name "Net-(LED1SW1-PadA)") (class "Default")
      (node (ref "LED1SW1") (pin "A") (pinfunction "A_A") (pintype "passive"))
      (node (ref "R2SW1") (pin "1") (pinfunction "1_1") (pintype "passive"))
    )
    (net (code "35") (name "Net-(LED1SW2-PadA)") (class "Default")
      (node (ref "LED1SW2") (pin "A") (pinfunction "A_A") (pintype "passive"))
      (node (ref "R2SW2") (pin "1") (pinfunction "1_1") (pintype "passive"))
    )
    (net (code "36") (name "Net-(LED4UC1-PadA)") (class "Default")
      (node (ref "LED4UC1") (pin "A") (pinfunction "A_A") (pintype "passive"))
      (node (ref "R16UC1") (pin "1") (pinfunction "1_1") (pintype "passive"))
    )
    (net (code "37") (name "Net-(LED5UC1-PadA)") (class "Default")
      (node (ref "LED5UC1") (pin "A") (pinfunction "A_A") (pintype "passive"))
      (node (ref "R17UC1") (pin "1") (pinfunction "1_1") (pintype "passive"))
    )
    (net (code "38") (name "Net-(LED6UC1-PadA)") (class "Default")
      (node (ref "LED6UC1") (pin "A") (pinfunction "A_A") (pintype "passive"))
      (node (ref "R18UC1") (pin "1") (pinfunction "1_1") (pintype "passive"))
    )
    (net (code "39") (name "Net-(LED7UC1-PadA)") (class "Default")
      (node (ref "LED7UC1") (pin "A") (pinfunction "A_A") (pintype "passive"))
      (node (ref "R19UC1") (pin "1") (pinfunction "1_1") (pintype "passive"))
    )
    (net (code "40") (name "Net-(Q1L-D)") (class "Default")
      (node (ref "H2L") (pin "3") (pinfunction "3_3") (pintype "passive"))
      (node (ref "Q1L") (pin "3") (pinfunction "D_3") (pintype "passive"))
    )
    (net (code "41") (name "Net-(Q1L-G)") (class "Default")
      (node (ref "Q1L") (pin "1") (pinfunction "G_1") (pintype "passive"))
      (node (ref "Q2L") (pin "3") (pinfunction "D_3") (pintype "passive"))
      (node (ref "R1L") (pin "1") (pinfunction "1_1") (pintype "passive"))
    )
    (net (code "42") (name "Net-(Q1P-D)") (class "Default")
      (node (ref "BATT2") (pin "-") (pinfunction "-_-") (pintype "power_in"))
      (node (ref "Q1P") (pin "3") (pinfunction "D_3") (pintype "passive"))
      (node (ref "R2P") (pin "1") (pinfunction "1_1") (pintype "passive"))
      (node (ref "SW1P") (pin "3") (pinfunction "3_3") (pintype "passive"))
    )
    (net (code "43") (name "Net-(Q2L-G)") (class "Default")
      (node (ref "Q2L") (pin "1") (pinfunction "G_1") (pintype "passive"))
      (node (ref "R2L") (pin "2") (pinfunction "2_2") (pintype "passive"))
    )
    (net (code "44") (name "Net-(Q2P-D)") (class "Default")
      (node (ref "C1P") (pin "1") (pinfunction "1_1") (pintype "passive"))
      (node (ref "LED1P") (pin "A") (pinfunction "A_A") (pintype "passive"))
      (node (ref "Q2P") (pin "3") (pinfunction "D_3") (pintype "passive"))
      (node (ref "VR11") (pin "IN") (pinfunction "IN_IN") (pintype "input"))
      (node (ref "VR12") (pin "3") (pinfunction "IN_3") (pintype "input"))
    )
    (net (code "45") (name "Net-(R1P-Pad1)") (class "Default")
      (node (ref "R1P") (pin "1") (pinfunction "1_1") (pintype "passive"))
      (node (ref "R2P") (pin "2") (pinfunction "2_2") (pintype "passive"))
      (node (ref "SW1P") (pin "1") (pinfunction "1_1") (pintype "passive"))
    )
    (net (code "46") (name "Net-(R1SW1-Pad2)") (class "Default")
      (node (ref "R1SW1") (pin "2") (pinfunction "2_2") (pintype "passive"))
      (node (ref "SW1") (pin "1") (pinfunction "1_1") (pintype "passive"))
    )
    (net (code "47") (name "Net-(R1SW2-Pad2)") (class "Default")
      (node (ref "R1SW2") (pin "2") (pinfunction "2_2") (pintype "passive"))
      (node (ref "SW2") (pin "1") (pinfunction "1_1") (pintype "passive"))
    )
    (net (code "48") (name "Net-(UC1-AREF)") (class "Default")
      (node (ref "C4UC1") (pin "1") (pinfunction "1_1") (pintype "passive"))
      (node (ref "UC1") (pin "21") (pinfunction "AREF_21") (pintype "input"))
    )
    (net (code "49") (name "PITCH") (class "Default")
      (node (ref "C2JS2") (pin "1") (pinfunction "1_1") (pintype "passive"))
      (node (ref "JS2") (pin "V2") (pinfunction "V_V2") (pintype "bidirectional"))
      (node (ref "UC1") (pin "24") (pinfunction "PC1_24") (pintype "bidirectional"))
    )
    (net (code "50") (name "RESET") (class "Default")
      (node (ref "B1UC1") (pin "1") (pinfunction "1_1") (pintype "passive"))
      (node (ref "C4UC2") (pin "2") (pinfunction "2_2") (pintype "passive"))
      (node (ref "C5UC1") (pin "2") (pinfunction "2_2") (pintype "passive"))
      (node (ref "H1L") (pin "5") (pinfunction "5_5") (pintype "passive"))
      (node (ref "ISP1UC1") (pin "5") (pinfunction "RST_5") (pintype "output"))
      (node (ref "ISP1UC2") (pin "5") (pinfunction "RST_5") (pintype "output"))
      (node (ref "R1UC1") (pin "1") (pinfunction "1_1") (pintype "passive"))
      (node (ref "UC1") (pin "1") (pinfunction "PC6_1") (pintype "bidirectional"))
      (node (ref "UC2") (pin "1") (pinfunction "PC6_1") (pintype "bidirectional"))
    )
    (net (code "51") (name "RIGHT_BUTTON") (class "Default")
      (node (ref "C4JS2") (pin "1") (pinfunction "1_1") (pintype "passive"))
      (node (ref "D1JS2") (pin "C") (pinfunction "C_C") (pintype "passive"))
      (node (ref "R2JS2") (pin "1") (pinfunction "1_1") (pintype "passive"))
      (node (ref "UC1") (pin "14") (pinfunction "PB0_14") (pintype "bidirectional"))
    )
    (net (code "52") (name "ROLL") (class "Default")
      (node (ref "C3JS2") (pin "1") (pinfunction "1_1") (pintype "passive"))
      (node (ref "JS2") (pin "H2") (pinfunction "H_H2") (pintype "bidirectional"))
      (node (ref "UC1") (pin "23") (pinfunction "PC0_23") (pintype "bidirectional"))
    )
    (net (code "53") (name "SCK1") (class "Default")
      (node (ref "B1") (pin "SCK") (pinfunction "SCK_SCK") (pintype "input"))
      (node (ref "ISP1UC1") (pin "3") (pinfunction "SCK_3") (pintype "output"))
      (node (ref "UC1") (pin "19") (pinfunction "PB5_19") (pintype "bidirectional"))
    )
    (net (code "54") (name "SCL") (class "Default")
      (node (ref "H1M") (pin "3") (pinfunction "3_3") (pintype "passive"))
      (node (ref "UC1") (pin "28") (pinfunction "PC5_28") (pintype "bidirectional"))
      (node (ref "UC2") (pin "28") (pinfunction "PC5_28") (pintype "bidirectional"))
    )
    (net (code "55") (name "SDA") (class "Default")
      (node (ref "H1M") (pin "4") (pinfunction "4_4") (pintype "passive"))
      (node (ref "UC1") (pin "27") (pinfunction "PC4_27") (pintype "bidirectional"))
      (node (ref "UC2") (pin "27") (pinfunction "PC4_27") (pintype "bidirectional"))
    )
    (net (code "56") (name "SD_DI") (class "Default")
      (node (ref "H4L") (pin "5") (pinfunction "5_5") (pintype "passive"))
      (node (ref "ISP1UC2") (pin "4") (pinfunction "MOSI_4") (pintype "output"))
      (node (ref "UC2") (pin "17") (pinfunction "PB3_17") (pintype "bidirectional"))
    )
    (net (code "57") (name "SD_DO") (class "Default")
      (node (ref "H4L") (pin "4") (pinfunction "4_4") (pintype "passive"))
      (node (ref "ISP1UC2") (pin "1") (pinfunction "MISO_1") (pintype "input"))
      (node (ref "UC2") (pin "18") (pinfunction "PB4_18") (pintype "bidirectional"))
    )
    (net (code "58") (name "SD_SCK") (class "Default")
      (node (ref "H4L") (pin "3") (pinfunction "3_3") (pintype "passive"))
      (node (ref "ISP1UC2") (pin "3") (pinfunction "SCK_3") (pintype "output"))
      (node (ref "UC2") (pin "19") (pinfunction "PB5_19") (pintype "bidirectional"))
    )
    (net (code "59") (name "SD_SS") (class "Default")
      (node (ref "H4L") (pin "6") (pinfunction "6_6") (pintype "passive"))
      (node (ref "UC2") (pin "16") (pinfunction "PB2_16") (pintype "bidirectional"))
    )
    (net (code "60") (name "SIGNAL_LED") (class "Default")
      (node (ref "R18UC1") (pin "2") (pinfunction "2_2") (pintype "passive"))
      (node (ref "R19UC1") (pin "2") (pinfunction "2_2") (pintype "passive"))
      (node (ref "UC1") (pin "12") (pinfunction "PD6_12") (pintype "bidirectional"))
    )
    (net (code "61") (name "THROTTLE") (class "Default")
      (node (ref "C2JS1") (pin "1") (pinfunction "1_1") (pintype "passive"))
      (node (ref "JS1") (pin "V2") (pinfunction "V_V2") (pintype "bidirectional"))
      (node (ref "P1JS1") (pin "MIDDLE") (pinfunction "MIDDLE_MIDDLE") (pintype "passive"))
      (node (ref "UC1") (pin "25") (pinfunction "PC2_25") (pintype "bidirectional"))
    )
    (net (code "62") (name "URX1") (class "Default")
      (node (ref "FTDI1UC1") (pin "TXO") (pinfunction "3_TXO") (pintype "passive"))
      (node (ref "UC1") (pin "2") (pinfunction "PD0_2") (pintype "bidirectional"))
    )
    (net (code "63") (name "URX2") (class "Default")
      (node (ref "FTDI1UC2") (pin "TXO") (pinfunction "3_TXO") (pintype "passive"))
      (node (ref "UC2") (pin "2") (pinfunction "PD0_2") (pintype "bidirectional"))
    )
    (net (code "64") (name "UTX1") (class "Default")
      (node (ref "FTDI1UC1") (pin "RXI") (pinfunction "2_RXI") (pintype "passive"))
      (node (ref "UC1") (pin "3") (pinfunction "PD1_3") (pintype "bidirectional"))
    )
    (net (code "65") (name "UTX2") (class "Default")
      (node (ref "FTDI1UC2") (pin "RXI") (pinfunction "2_RXI") (pintype "passive"))
      (node (ref "UC2") (pin "3") (pinfunction "PD1_3") (pintype "bidirectional"))
    )
    (net (code "66") (name "VCC") (class "Default")
      (node (ref "BATT1") (pin "+") (pinfunction "+_+") (pintype "power_in"))
      (node (ref "Q1P") (pin "1") (pinfunction "G_1") (pintype "passive"))
      (node (ref "Q2P") (pin "2") (pinfunction "S_2") (pintype "passive"))
      (node (ref "R1P") (pin "2") (pinfunction "2_2") (pintype "passive"))
      (node (ref "R3P") (pin "2") (pinfunction "2_2") (pintype "passive"))
    )
    (net (code "67") (name "WARNING_LED") (class "Default")
      (node (ref "R16UC1") (pin "2") (pinfunction "2_2") (pintype "passive"))
      (node (ref "R17UC1") (pin "2") (pinfunction "2_2") (pintype "passive"))
      (node (ref "UC1") (pin "11") (pinfunction "PD5_11") (pintype "bidirectional"))
    )
    (net (code "68") (name "XTAL11") (class "Default")
      (node (ref "C1X1") (pin "1") (pinfunction "1_1") (pintype "passive"))
      (node (ref "UC1") (pin "9") (pinfunction "PB6_9") (pintype "bidirectional"))
      (node (ref "XTAL1UC1") (pin "1") (pinfunction "1_1") (pintype "passive"))
    )
    (net (code "69") (name "XTAL12") (class "Default")
      (node (ref "C2X1") (pin "1") (pinfunction "1_1") (pintype "passive"))
      (node (ref "UC1") (pin "10") (pinfunction "PB7_10") (pintype "bidirectional"))
      (node (ref "XTAL1UC1") (pin "2") (pinfunction "2_2") (pintype "passive"))
    )
    (net (code "70") (name "XTAL21") (class "Default")
      (node (ref "C1X2") (pin "1") (pinfunction "1_1") (pintype "passive"))
      (node (ref "UC2") (pin "9") (pinfunction "PB6_9") (pintype "bidirectional"))
      (node (ref "XTAL1UC2") (pin "1") (pinfunction "1_1") (pintype "passive"))
    )
    (net (code "71") (name "XTAL22") (class "Default")
      (node (ref "C2X2") (pin "1") (pinfunction "1_1") (pintype "passive"))
      (node (ref "UC2") (pin "10") (pinfunction "PB7_10") (pintype "bidirectional"))
      (node (ref "XTAL1UC2") (pin "2") (pinfunction "2_2") (pintype "passive"))
    )
    (net (code "72") (name "YAW") (class "Default")
      (node (ref "C3JS1") (pin "1") (pinfunction "1_1") (pintype "passive"))
      (node (ref "JS1") (pin "H2") (pinfunction "H_H2") (pintype "bidirectional"))
      (node (ref "UC1") (pin "26") (pinfunction "PC3_26") (pintype "bidirectional"))
    )
    (net (code "73") (name "unconnected-(B1-PadIRQ)") (class "Default")
      (node (ref "B1") (pin "IRQ") (pinfunction "IRQ_IRQ") (pintype "output"))
    )
    (net (code "74") (name "unconnected-(B2JS1-P-Pad3)") (class "Default")
      (node (ref "B2JS1") (pin "3") (pinfunction "P_3") (pintype "passive"))
    )
    (net (code "75") (name "unconnected-(B2JS1-S1-Pad2)") (class "Default")
      (node (ref "B2JS1") (pin "2") (pinfunction "S1_2") (pintype "passive"))
    )
    (net (code "76") (name "unconnected-(FTDI1UC1-5-PadCTS)") (class "Default")
      (node (ref "FTDI1UC1") (pin "CTS") (pinfunction "5_CTS") (pintype "passive"))
    )
    (net (code "77") (name "unconnected-(FTDI1UC2-5-PadCTS)") (class "Default")
      (node (ref "FTDI1UC2") (pin "CTS") (pinfunction "5_CTS") (pintype "passive"))
    )
    (net (code "78") (name "unconnected-(H1L-Pad6)") (class "Default")
      (node (ref "H1L") (pin "6") (pinfunction "6_6") (pintype "passive"))
    )
    (net (code "79") (name "unconnected-(H1M-Pad5)") (class "Default")
      (node (ref "H1M") (pin "5") (pinfunction "5_5") (pintype "passive"))
    )
    (net (code "80") (name "unconnected-(H1M-Pad6)") (class "Default")
      (node (ref "H1M") (pin "6") (pinfunction "6_6") (pintype "passive"))
    )
    (net (code "81") (name "unconnected-(H1M-Pad8)") (class "Default")
      (node (ref "H1M") (pin "8") (pinfunction "8_8") (pintype "passive"))
    )
    (net (code "82") (name "unconnected-(H2L-Pad1)") (class "Default")
      (node (ref "H2L") (pin "1") (pinfunction "1_1") (pintype "passive"))
    )
    (net (code "83") (name "unconnected-(H2L-Pad4)") (class "Default")
      (node (ref "H2L") (pin "4") (pinfunction "4_4") (pintype "passive"))
    )
    (net (code "84") (name "unconnected-(H2L-Pad6)") (class "Default")
      (node (ref "H2L") (pin "6") (pinfunction "6_6") (pintype "passive"))
    )
    (net (code "85") (name "unconnected-(H3L-Pad7)") (class "Default")
      (node (ref "H3L") (pin "7") (pinfunction "7_7") (pintype "passive"))
    )
    (net (code "86") (name "unconnected-(H3L-Pad8)") (class "Default")
      (node (ref "H3L") (pin "8") (pinfunction "8_8") (pintype "passive"))
    )
    (net (code "87") (name "unconnected-(H4L-Pad1)") (class "Default")
      (node (ref "H4L") (pin "1") (pinfunction "1_1") (pintype "passive"))
    )
    (net (code "88") (name "unconnected-(H4L-Pad2)") (class "Default")
      (node (ref "H4L") (pin "2") (pinfunction "2_2") (pintype "passive"))
    )
    (net (code "89") (name "unconnected-(UC2-AREF-Pad21)") (class "Default")
      (node (ref "UC2") (pin "21") (pinfunction "AREF_21") (pintype "input"))
    )
  )
)
